# Button_Breakout_Schematic.net
KiCad netlist of a schematic drawn in EAGLE
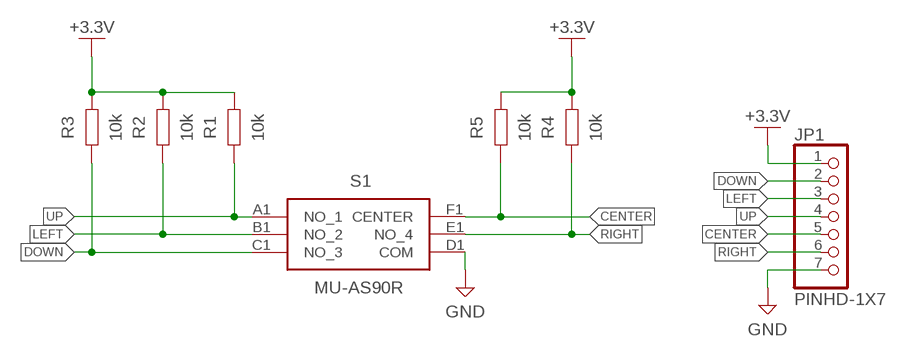
[diagram p0: schematic, sheet 1]

(export (version "E")
  (design (tool "Eeschema 10.0.6"))
  (components
    (comp (ref "JP1")
      (value "PINHD-1X7")
      (footprint "eagle-import:1X07")
      (libsource (lib "eagle-import") (part "PINHD-1X7"))
    )
    (comp (ref "R1")
      (value "10k")
      (footprint "eagle-import:RESC1608X60")
      (libsource (lib "eagle-import") (part "RCHIP-0603(1608-METRIC)_"))
    )
    (comp (ref "R2")
      (value "10k")
      (footprint "eagle-import:RESC1608X60")
      (libsource (lib "eagle-import") (part "RCHIP-0603(1608-METRIC)_"))
    )
    (comp (ref "R3")
      (value "10k")
      (footprint "eagle-import:RESC1608X60")
      (libsource (lib "eagle-import") (part "RCHIP-0603(1608-METRIC)_"))
    )
    (comp (ref "R4")
      (value "10k")
      (footprint "eagle-import:RESC1608X60")
      (libsource (lib "eagle-import") (part "RCHIP-0603(1608-METRIC)_"))
    )
    (comp (ref "R5")
      (value "10k")
      (footprint "eagle-import:RESC1608X60")
      (libsource (lib "eagle-import") (part "RCHIP-0603(1608-METRIC)_"))
    )
    (comp (ref "S1")
      (value "MU-AS90R")
      (footprint "eagle-import:MUAS90R")
      (fields (field (name "MOUSER_PART_NUMBER") "642-MU-AS90R"))
      (libsource (lib "eagle-import") (part "MU-AS90R"))
    )
  )
  (nets
    (net (code "1") (name "+3.3V") (class "Default")
      (node (ref "JP1") (pin "1") (pinfunction "1_1") (pintype "passive"))
      (node (ref "R1") (pin "2") (pinfunction "2_2") (pintype "passive"))
      (node (ref "R2") (pin "2") (pinfunction "2_2") (pintype "passive"))
      (node (ref "R3") (pin "2") (pinfunction "2_2") (pintype "passive"))
      (node (ref "R4") (pin "2") (pinfunction "2_2") (pintype "passive"))
      (node (ref "R5") (pin "2") (pinfunction "2_2") (pintype "passive"))
    )
    (net (code "2") (name "CENTER") (class "Default")
      (node (ref "JP1") (pin "5") (pinfunction "5_5") (pintype "passive"))
      (node (ref "R5") (pin "1") (pinfunction "1_1") (pintype "passive"))
      (node (ref "S1") (pin "F1") (pinfunction "CENTER_F1") (pintype "bidirectional"))
    )
    (net (code "3") (name "DOWN") (class "Default")
      (node (ref "JP1") (pin "2") (pinfunction "2_2") (pintype "passive"))
      (node (ref "R3") (pin "1") (pinfunction "1_1") (pintype "passive"))
      (node (ref "S1") (pin "C1") (pinfunction "NO_3_C1") (pintype "bidirectional"))
    )
    (net (code "4") (name "GND") (class "Default")
      (node (ref "JP1") (pin "7") (pinfunction "7_7") (pintype "passive"))
      (node (ref "S1") (pin "D1") (pinfunction "COM_D1") (pintype "bidirectional"))
    )
    (net (code "5") (name "LEFT") (class "Default")
      (node (ref "JP1") (pin "3") (pinfunction "3_3") (pintype "passive"))
      (node (ref "R2") (pin "1") (pinfunction "1_1") (pintype "passive"))
      (node (ref "S1") (pin "B1") (pinfunction "NO_2_B1") (pintype "bidirectional"))
    )
    (net (code "6") (name "RIGHT") (class "Default")
      (node (ref "JP1") (pin "6") (pinfunction "6_6") (pintype "passive"))
      (node (ref "R4") (pin "1") (pinfunction "1_1") (pintype "passive"))
      (node (ref "S1") (pin "E1") (pinfunction "NO_4_E1") (pintype "bidirectional"))
    )
    (net (code "7") (name "UP") (class "Default")
      (node (ref "JP1") (pin "4") (pinfunction "4_4") (pintype "passive"))
      (node (ref "R1") (pin "1") (pinfunction "1_1") (pintype "passive"))
      (node (ref "S1") (pin "A1") (pinfunction "NO_1_A1") (pintype "bidirectional"))
    )
  )
)
